# AFE4220.net
KiCad netlist of a schematic drawn in Altium Designer
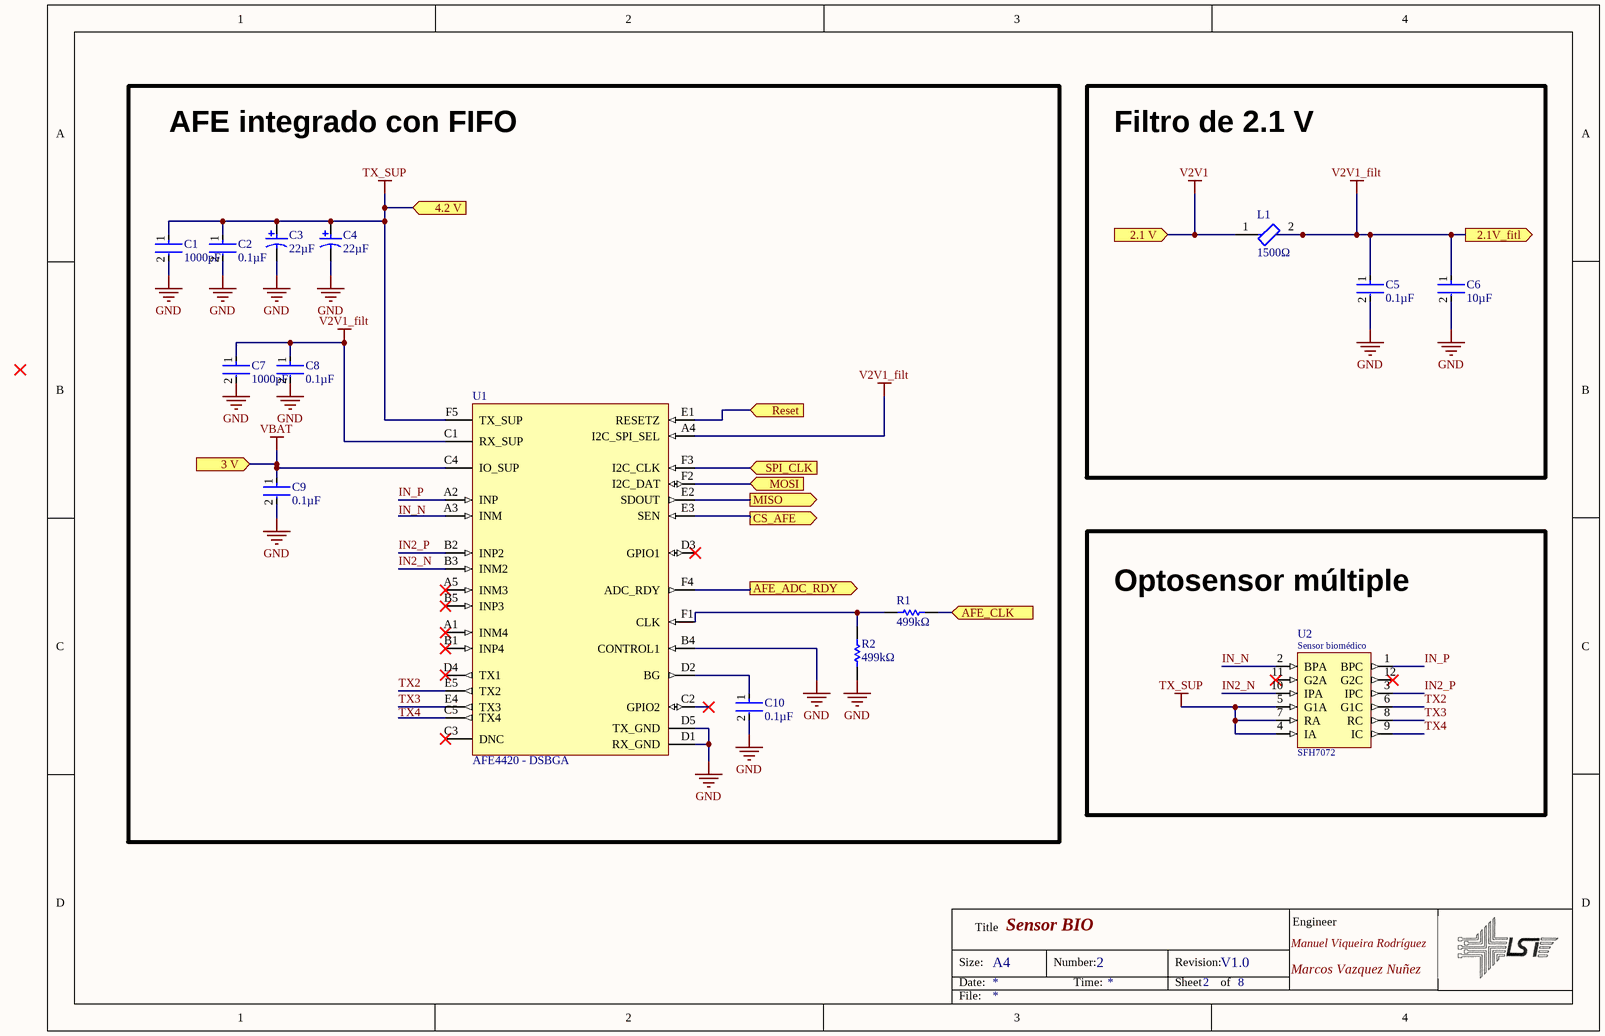
[diagram p0: AFE4220.SchDoc]

(export (version "E")
  (design (tool "Eeschema 10.0.6"))
  (components
    (comp (ref "C1")
      (value "1000pF")
      (footprint "FP-CL10-IPC_B")
      (description "Cap Ceramic 10uF 10V X5R ±10% Pad SMD 0603 +85°C T/R")
      (fields (field (name "TOLERANCE") "10%"))
      (libsource (lib "Altium Content Vault") (part "b4654b650e69147ec39a6b967a45e02"))
    )
    (comp (ref "C2")
      (value "0.1µF")
      (footprint "FP-CL10-IPC_B")
      (description "Cap Ceramic 10uF 10V X5R ±10% Pad SMD 0603 +85°C T/R")
      (fields (field (name "TOLERANCE") "10%"))
      (libsource (lib "Altium Content Vault") (part "b4654b650e69147ec39a6b967a45e02"))
    )
    (comp (ref "C3")
      (value "22µF")
      (footprint "NIC-CAPA2-4X5.8_V")
      (fields (field (name "MANUFACTURER") "Nichicon") (field (name "PARTNUMBER") "UUD1A220MCL1GS"))
      (libsource (lib "Altium Content Vault") (part "NIC-CAP-P-2"))
    )
    (comp (ref "C4")
      (value "22µF")
      (footprint "NIC-CAPA2-4X5.8_V")
      (fields (field (name "MANUFACTURER") "Nichicon") (field (name "PARTNUMBER") "UUD1A220MCL1GS"))
      (libsource (lib "Altium Content Vault") (part "NIC-CAP-P-2"))
    )
    (comp (ref "C5")
      (value "0.1µF")
      (footprint "FP-CL10-IPC_B")
      (description "Cap Ceramic 10uF 10V X5R ±10% Pad SMD 0603 +85°C T/R")
      (fields (field (name "TOLERANCE") "10%"))
      (libsource (lib "Altium Content Vault") (part "b4654b650e69147ec39a6b967a45e02"))
    )
    (comp (ref "C6")
      (value "10µF")
      (footprint "FP-CL10-IPC_B")
      (description "Cap Ceramic 10uF 10V X5R ±10% Pad SMD 0603 +85°C T/R")
      (fields (field (name "TOLERANCE") "10%"))
      (libsource (lib "Altium Content Vault") (part "b4654b650e69147ec39a6b967a45e02"))
    )
    (comp (ref "C7")
      (value "1000pF")
      (footprint "FP-CL10-IPC_B")
      (description "Cap Ceramic 10uF 10V X5R ±10% Pad SMD 0603 +85°C T/R")
      (fields (field (name "TOLERANCE") "10%"))
      (libsource (lib "Altium Content Vault") (part "b4654b650e69147ec39a6b967a45e02"))
    )
    (comp (ref "C8")
      (value "0.1µF")
      (footprint "FP-CL10-IPC_B")
      (description "Cap Ceramic 10uF 10V X5R ±10% Pad SMD 0603 +85°C T/R")
      (fields (field (name "TOLERANCE") "10%"))
      (libsource (lib "Altium Content Vault") (part "b4654b650e69147ec39a6b967a45e02"))
    )
    (comp (ref "C9")
      (value "0.1µF")
      (footprint "FP-CL10-IPC_B")
      (description "Cap Ceramic 10uF 10V X5R ±10% Pad SMD 0603 +85°C T/R")
      (fields (field (name "TOLERANCE") "10%"))
      (libsource (lib "Altium Content Vault") (part "b4654b650e69147ec39a6b967a45e02"))
    )
    (comp (ref "C10")
      (value "0.1µF")
      (footprint "FP-CL10-IPC_B")
      (description "Cap Ceramic 10uF 10V X5R ±10% Pad SMD 0603 +85°C T/R")
      (fields (field (name "TOLERANCE") "10%"))
      (libsource (lib "Altium Content Vault") (part "b4654b650e69147ec39a6b967a45e02"))
    )
    (comp (ref "L1")
      (value "1500Ω")
      (footprint "FP-BLM18-0_15-t0_8-IPC_C")
      (description "Chip Ferrite Bead, 0603, 1500Ω @ 100MHz, 0.5Ω, 25%, 500mA")
      (fields (field (name "TOLERANCE") "25%"))
      (libsource (lib "Altium Content Vault") (part "5f30dd21d616792df468990f7003faa"))
    )
    (comp (ref "R1")
      (value "499kΩ")
      (footprint "RESC1005X40X25NL05T10")
      (fields (field (name "PART NUMBER") "ERJ-U02F1501X") (field (name "MANUFACTURER") "Panasonic"))
      (libsource (lib "Altium Content Vault") (part "RES"))
    )
    (comp (ref "R2")
      (value "499kΩ")
      (footprint "RESC1005X40X25NL05T10")
      (fields (field (name "PART NUMBER") "ERJ-U02F1501X") (field (name "MANUFACTURER") "Panasonic"))
      (libsource (lib "Altium Content Vault") (part "RES"))
    )
    (comp (ref "U1")
      (value "AFE4420 - DSBGA")
      (footprint "AFE4420 - DSBGA")
      (libsource (lib "DEOP2021") (part "AFE4420 - DSBGA"))
    )
    (comp (ref "U2")
      (value "~")
      (footprint "SFH7072")
      (description "Sensor biométrico")
      (libsource (lib "DEOP2021") (part "SFH7072"))
    )
  )
  (nets
    (net (code "1") (name "/AFE_ADC_RDY") (class "Default")
      (node (ref "U1") (pin "F4") (pinfunction "ADC_RDY_F4") (pintype "output"))
    )
    (net (code "2") (name "/AFE_CLK") (class "Default")
      (node (ref "R1") (pin "2") (pinfunction "2_2") (pintype "passive"))
    )
    (net (code "3") (name "/CS_AFE") (class "Default")
      (node (ref "U1") (pin "E3") (pinfunction "SEN_E3") (pintype "input"))
    )
    (net (code "4") (name "/IN2_N") (class "Default")
      (node (ref "U1") (pin "B3") (pinfunction "INM2_B3") (pintype "input"))
      (node (ref "U2") (pin "10") (pinfunction "IPA_10") (pintype "input"))
    )
    (net (code "5") (name "/IN2_P") (class "Default")
      (node (ref "U1") (pin "B2") (pinfunction "INP2_B2") (pintype "input"))
      (node (ref "U2") (pin "3") (pinfunction "IPC_3") (pintype "output"))
    )
    (net (code "6") (name "/IN_N") (class "Default")
      (node (ref "U2") (pin "2") (pinfunction "BPA_2") (pintype "input"))
    )
    (net (code "7") (name "/IN_P") (class "Default")
      (node (ref "U1") (pin "A2") (pinfunction "INP_A2") (pintype "input"))
      (node (ref "U2") (pin "1") (pinfunction "BPC_1") (pintype "output"))
    )
    (net (code "8") (name "/MISO") (class "Default")
      (node (ref "U1") (pin "E2") (pinfunction "SDOUT_E2") (pintype "output"))
    )
    (net (code "9") (name "/MOSI") (class "Default")
      (node (ref "U1") (pin "F2") (pinfunction "I2C_DAT_F2") (pintype "bidirectional"))
    )
    (net (code "10") (name "/Reset") (class "Default")
      (node (ref "U1") (pin "E1") (pinfunction "RESETZ_E1") (pintype "input"))
    )
    (net (code "11") (name "/SPI_CLK") (class "Default")
      (node (ref "U1") (pin "F3") (pinfunction "I2C_CLK_F3") (pintype "input"))
    )
    (net (code "12") (name "/TX2") (class "Default")
      (node (ref "U1") (pin "E5") (pinfunction "TX2_E5") (pintype "output"))
      (node (ref "U2") (pin "6") (pinfunction "G1C_6") (pintype "output"))
    )
    (net (code "13") (name "/TX3") (class "Default")
      (node (ref "U1") (pin "E4") (pinfunction "TX3_E4") (pintype "output"))
      (node (ref "U2") (pin "8") (pinfunction "RC_8") (pintype "output"))
    )
    (net (code "14") (name "/TX4") (class "Default")
      (node (ref "U2") (pin "9") (pinfunction "IC_9") (pintype "output"))
    )
    (net (code "15") (name "GND") (class "Default")
      (node (ref "C1") (pin "2") (pinfunction "2_2") (pintype "passive"))
      (node (ref "C10") (pin "2") (pinfunction "2_2") (pintype "passive"))
      (node (ref "C2") (pin "2") (pinfunction "2_2") (pintype "passive"))
      (node (ref "C3") (pin "2") (pinfunction "2_2") (pintype "passive"))
      (node (ref "C4") (pin "2") (pinfunction "2_2") (pintype "passive"))
      (node (ref "C5") (pin "2") (pinfunction "2_2") (pintype "passive"))
      (node (ref "C6") (pin "2") (pinfunction "2_2") (pintype "passive"))
      (node (ref "C7") (pin "2") (pinfunction "2_2") (pintype "passive"))
      (node (ref "C8") (pin "2") (pinfunction "2_2") (pintype "passive"))
      (node (ref "C9") (pin "2") (pinfunction "2_2") (pintype "passive"))
      (node (ref "R2") (pin "1") (pinfunction "1_1") (pintype "passive"))
      (node (ref "U1") (pin "B4") (pinfunction "CONTROL1_B4") (pintype "input"))
      (node (ref "U1") (pin "D1") (pinfunction "RX_GND_D1") (pintype "power_in"))
      (node (ref "U1") (pin "D5") (pinfunction "TX_GND_D5") (pintype "power_in"))
    )
    (net (code "16") (name "Net-(U1-BG)") (class "Default")
      (node (ref "C10") (pin "1") (pinfunction "1_1") (pintype "passive"))
      (node (ref "U1") (pin "D2") (pinfunction "BG_D2") (pintype "output"))
    )
    (net (code "17") (name "Net-(U1-CLK)") (class "Default")
      (node (ref "R1") (pin "1") (pinfunction "1_1") (pintype "passive"))
      (node (ref "R2") (pin "2") (pinfunction "2_2") (pintype "passive"))
      (node (ref "U1") (pin "F1") (pinfunction "CLK_F1") (pintype "input"))
    )
    (net (code "18") (name "TX_SUP") (class "Default")
      (node (ref "C1") (pin "1") (pinfunction "1_1") (pintype "passive"))
      (node (ref "C2") (pin "1") (pinfunction "1_1") (pintype "passive"))
      (node (ref "C3") (pin "1") (pinfunction "1_1") (pintype "passive"))
      (node (ref "C4") (pin "1") (pinfunction "1_1") (pintype "passive"))
      (node (ref "U1") (pin "F5") (pinfunction "TX_SUP_F5") (pintype "power_in"))
      (node (ref "U2") (pin "4") (pinfunction "IA_4") (pintype "input"))
      (node (ref "U2") (pin "5") (pinfunction "G1A_5") (pintype "input"))
      (node (ref "U2") (pin "7") (pinfunction "RA_7") (pintype "input"))
    )
    (net (code "19") (name "V2V1") (class "Default")
      (node (ref "L1") (pin "1") (pinfunction "1_1") (pintype "passive"))
    )
    (net (code "20") (name "V2V1_filt") (class "Default")
      (node (ref "C5") (pin "1") (pinfunction "1_1") (pintype "passive"))
      (node (ref "C6") (pin "1") (pinfunction "1_1") (pintype "passive"))
      (node (ref "C7") (pin "1") (pinfunction "1_1") (pintype "passive"))
      (node (ref "C8") (pin "1") (pinfunction "1_1") (pintype "passive"))
      (node (ref "L1") (pin "2") (pinfunction "2_2") (pintype "passive"))
      (node (ref "U1") (pin "A4") (pinfunction "I2C_SPI_SEL_A4") (pintype "input"))
      (node (ref "U1") (pin "C1") (pinfunction "RX_SUP_C1") (pintype "power_in"))
    )
    (net (code "21") (name "VBAT") (class "Default")
      (node (ref "C9") (pin "1") (pinfunction "1_1") (pintype "passive"))
      (node (ref "U1") (pin "C4") (pinfunction "IO_SUP_C4") (pintype "power_in"))
    )
    (net (code "22") (name "unconnected-(U1-DNC-PadC3)") (class "Default")
      (node (ref "U1") (pin "C3") (pinfunction "DNC_C3") (pintype "passive+no_connect"))
    )
    (net (code "23") (name "unconnected-(U1-GPIO1-PadD3)") (class "Default")
      (node (ref "U1") (pin "D3") (pinfunction "GPIO1_D3") (pintype "bidirectional+no_connect"))
    )
    (net (code "24") (name "unconnected-(U1-GPIO2-PadC2)") (class "Default")
      (node (ref "U1") (pin "C2") (pinfunction "GPIO2_C2") (pintype "bidirectional+no_connect"))
    )
    (net (code "25") (name "unconnected-(U1-INM-PadA3)") (class "Default")
      (node (ref "U1") (pin "A3") (pinfunction "INM_A3") (pintype "input"))
    )
    (net (code "26") (name "unconnected-(U1-INM3-PadA5)") (class "Default")
      (node (ref "U1") (pin "A5") (pinfunction "INM3_A5") (pintype "input+no_connect"))
    )
    (net (code "27") (name "unconnected-(U1-INM4-PadA1)") (class "Default")
      (node (ref "U1") (pin "A1") (pinfunction "INM4_A1") (pintype "input+no_connect"))
    )
    (net (code "28") (name "unconnected-(U1-INP3-PadB5)") (class "Default")
      (node (ref "U1") (pin "B5") (pinfunction "INP3_B5") (pintype "input+no_connect"))
    )
    (net (code "29") (name "unconnected-(U1-INP4-PadB1)") (class "Default")
      (node (ref "U1") (pin "B1") (pinfunction "INP4_B1") (pintype "input+no_connect"))
    )
    (net (code "30") (name "unconnected-(U1-TX1-PadD4)") (class "Default")
      (node (ref "U1") (pin "D4") (pinfunction "TX1_D4") (pintype "output+no_connect"))
    )
    (net (code "31") (name "unconnected-(U1-TX4-PadC5)") (class "Default")
      (node (ref "U1") (pin "C5") (pinfunction "TX4_C5") (pintype "output"))
    )
    (net (code "32") (name "unconnected-(U2-G2A-Pad11)") (class "Default")
      (node (ref "U2") (pin "11") (pinfunction "G2A_11") (pintype "input+no_connect"))
    )
    (net (code "33") (name "unconnected-(U2-G2C-Pad12)") (class "Default")
      (node (ref "U2") (pin "12") (pinfunction "G2C_12") (pintype "output+no_connect"))
    )
  )
)
